# KNX-MultiExt.net
KiCad netlist of a schematic drawn in Altium Designer
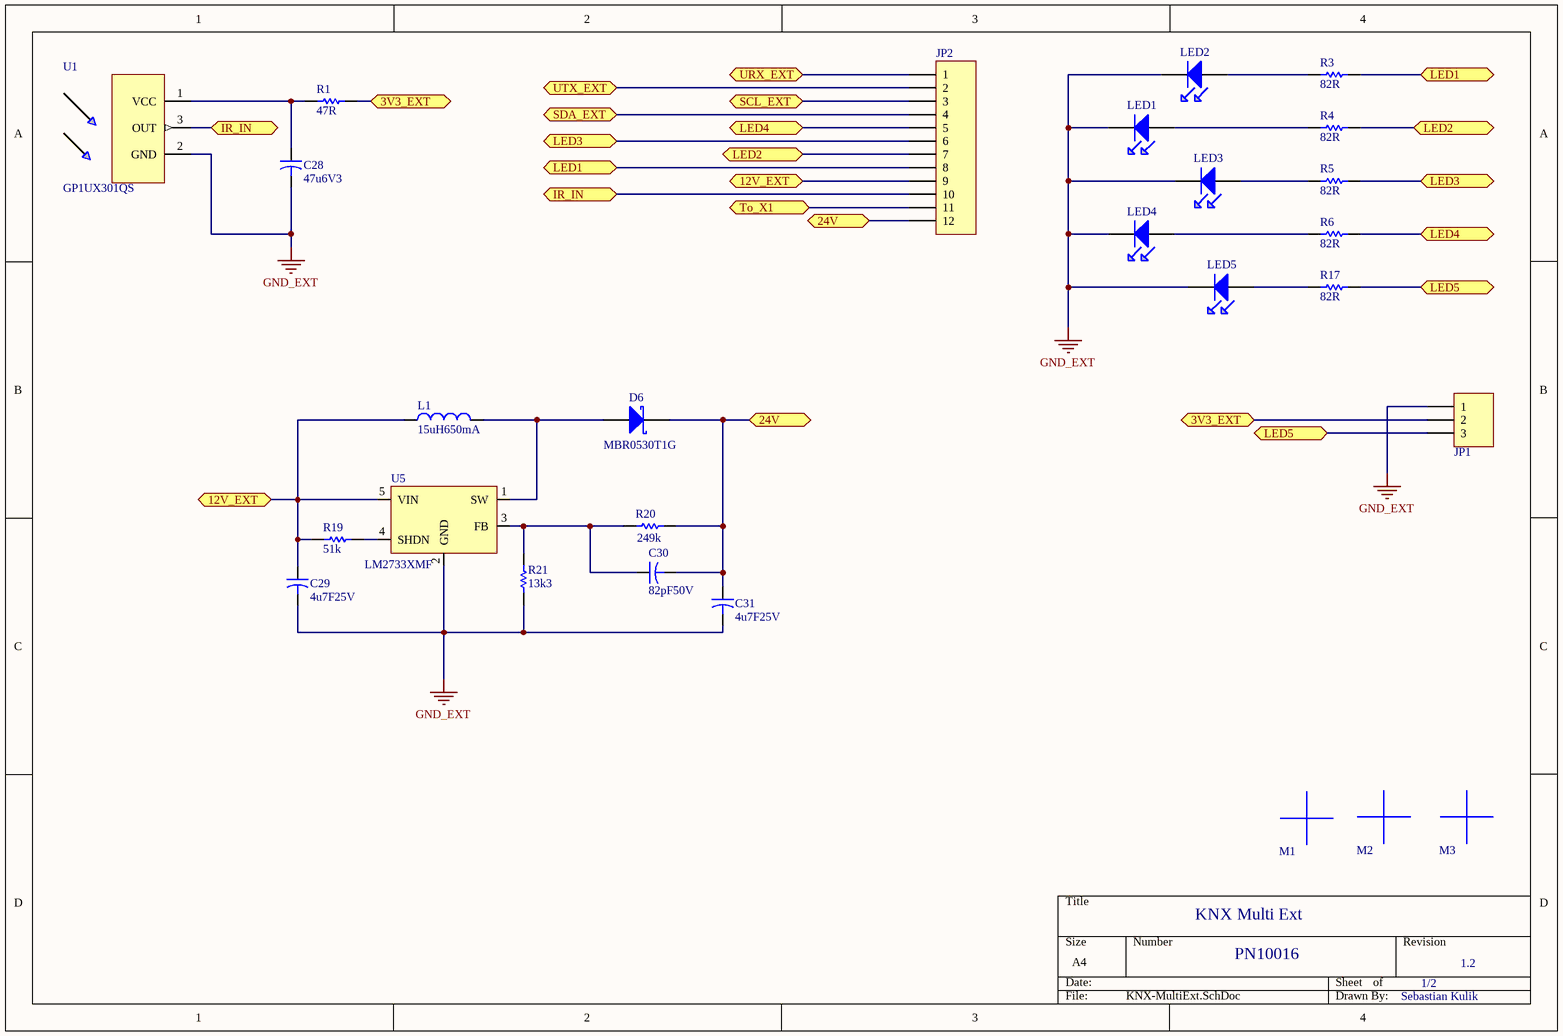
[diagram p0: KNX-MultiExt.SchDoc]

(export (version "E")
  (design (tool "Eeschema 10.0.6"))
  (components
    (comp (ref "C28")
      (value "47u6V3")
      (footprint "C0805")
      (description "Kemet  C series, X5R, 20%, 6.3V")
      (fields
        (field (name "MANUFACTURER") "Kemet")
        (field (name "Comment") "47u6V3_0805")
        (field (name "PUBLISHER") "Sebastian Kulik")
      )
      (libsource (lib "Capacitors") (part "47u6V3_0805"))
    )
    (comp (ref "C29")
      (value "4u7F25V")
      (footprint "C0805")
      (description "GRM series, X5R, 10%, 25V")
      (fields
        (field (name "MANUFACTURER") "Murata")
        (field (name "Comment") "4u7F25V_0805_Murata")
        (field (name "PUBLISHER") "Sebastian Kulik")
      )
      (libsource (lib "Capacitors") (part "4u7F25V_0805_Murata"))
    )
    (comp (ref "C30")
      (value "82pF50V")
      (footprint "C0805")
      (description "C0G series, 5%, 50V")
      (fields
        (field (name "MANUFACTURER") "AVX")
        (field (name "Comment") "82pF50V_0805")
        (field (name "PUBLISHER") "Sebastian Kulik")
      )
      (libsource (lib "Capacitors") (part "82pF50V_0805"))
    )
    (comp (ref "C31")
      (value "4u7F25V")
      (footprint "C0805")
      (description "GRM series, X7R, 10%, 50V")
      (fields
        (field (name "MANUFACTURER") "Murata")
        (field (name "Comment") "4u7F25V_0805_Murata_X7")
        (field (name "PUBLISHER") "Sebastian Kulik")
      )
      (libsource (lib "Capacitors") (part "4u7F25V_0805_Murata_X7"))
    )
    (comp (ref "D6")
      (value "MBR0530T1G")
      (footprint "SOD123")
      (description "Diode Schottky,2A,40V")
      (fields (field (name "MANUFACTURER") "Rohm") (field (name "PUBLISHER") "Sebastian Kulik"))
      (libsource (lib "Discrete") (part "MBR0530T1G"))
    )
    (comp (ref "JP1")
      (value "Plug_3_90_2.54")
      (footprint "HDR1X3-DOWN")
      (description "Plug,-3-Pin")
      (fields (field (name "MANUFACTURER") "WE") (field (name "PUBLISHER") "Sebastian Kulik"))
      (libsource (lib "Connectors") (part "Plug_3_90_2.54"))
    )
    (comp (ref "JP2")
      (value "Plug_12_90_2.54")
      (footprint "HDR1X12_2.54-Down")
      (description "Plug, 11-Pin")
      (fields (field (name "MANUFACTURER") "WE") (field (name "PUBLISHER") "Sebastian Kulik"))
      (libsource (lib "Connectors") (part "Plug_12_90_2.54"))
    )
    (comp (ref "L1")
      (value "15uH650mA")
      (footprint "WE-TPC-3816")
      (description "Coil, 15uH, 0.65A")
      (fields
        (field (name "MANUFACTURER") "WE")
        (field (name "Comment") "15uH-WE-TPC")
        (field (name "PUBLISHER") "Sebastian Kulik")
      )
      (libsource (lib "Passives") (part "15uH-WE-TPC"))
    )
    (comp (ref "LED1")
      (value "HSMG-120-Y")
      (footprint "HSMA-120-OR")
      (description "LED, 90°, yellow")
      (fields (field (name "MANUFACTURER") "Avago") (field (name "PUBLISHER") "Sebastian Kulik"))
      (libsource (lib "Discrete") (part "HSMG-120-Y"))
    )
    (comp (ref "LED2")
      (value "HSMG-120-GR")
      (footprint "HSMA-120-G")
      (description "LED, 90°, green")
      (fields (field (name "MANUFACTURER") "Avago") (field (name "PUBLISHER") "Sebastian Kulik"))
      (libsource (lib "Discrete") (part "HSMG-120-GR"))
    )
    (comp (ref "LED3")
      (value "HSMG-120-Y")
      (footprint "HSMA-120-OR")
      (description "LED, 90°, yellow")
      (fields (field (name "MANUFACTURER") "Avago") (field (name "PUBLISHER") "Sebastian Kulik"))
      (libsource (lib "Discrete") (part "HSMG-120-Y"))
    )
    (comp (ref "LED4")
      (value "HSMG-120-Y")
      (footprint "HSMA-120-OR")
      (description "LED, 90°, yellow")
      (fields (field (name "MANUFACTURER") "Avago") (field (name "PUBLISHER") "Sebastian Kulik"))
      (libsource (lib "Discrete") (part "HSMG-120-Y"))
    )
    (comp (ref "LED5")
      (value "HSMG-120-Y")
      (footprint "HSMA-120-OR")
      (description "LED, 90°, yellow")
      (fields (field (name "MANUFACTURER") "Avago") (field (name "PUBLISHER") "Sebastian Kulik"))
      (libsource (lib "Discrete") (part "HSMG-120-Y"))
    )
    (comp (ref "M1") (value "Mark") (footprint "Mark-3mm") (libsource (lib "Symbols") (part "Mark")))
    (comp (ref "M2") (value "Mark") (footprint "Mark-3mm") (libsource (lib "Symbols") (part "Mark")))
    (comp (ref "M3") (value "Mark") (footprint "Mark-3mm") (libsource (lib "Symbols") (part "Mark")))
    (comp (ref "R1")
      (value "47R")
      (footprint "R0603(1608)")
      (description "Vishay, CRCW series, 100mW, 1%")
      (fields
        (field (name "MANUFACTURER") "Vishay")
        (field (name "Comment") "47R_0603")
        (field (name "PUBLISHER") "Sebastian Kulik")
      )
      (libsource (lib "Resistors") (part "47R_0603"))
    )
    (comp (ref "R3")
      (value "82R")
      (footprint "R0603(1608)")
      (description "Vishay, CRCW series, 100mW, 1%")
      (fields
        (field (name "MANUFACTURER") "Vishay")
        (field (name "Comment") "82R_0603")
        (field (name "PUBLISHER") "Sebastian Kulik")
      )
      (libsource (lib "Resistors") (part "82R_0603"))
    )
    (comp (ref "R4")
      (value "82R")
      (footprint "R0603(1608)")
      (description "Vishay, CRCW series, 100mW, 1%")
      (fields
        (field (name "MANUFACTURER") "Vishay")
        (field (name "Comment") "82R_0603")
        (field (name "PUBLISHER") "Sebastian Kulik")
      )
      (libsource (lib "Resistors") (part "82R_0603"))
    )
    (comp (ref "R5")
      (value "82R")
      (footprint "R0603(1608)")
      (description "Vishay, CRCW series, 100mW, 1%")
      (fields
        (field (name "MANUFACTURER") "Vishay")
        (field (name "Comment") "82R_0603")
        (field (name "PUBLISHER") "Sebastian Kulik")
      )
      (libsource (lib "Resistors") (part "82R_0603"))
    )
    (comp (ref "R6")
      (value "82R")
      (footprint "R0603(1608)")
      (description "Vishay, CRCW series, 100mW, 1%")
      (fields
        (field (name "MANUFACTURER") "Vishay")
        (field (name "Comment") "82R_0603")
        (field (name "PUBLISHER") "Sebastian Kulik")
      )
      (libsource (lib "Resistors") (part "82R_0603"))
    )
    (comp (ref "R17")
      (value "82R")
      (footprint "R0603(1608)")
      (description "Vishay, CRCW series, 100mW, 1%")
      (fields
        (field (name "MANUFACTURER") "Vishay")
        (field (name "Comment") "82R_0603")
        (field (name "PUBLISHER") "Sebastian Kulik")
      )
      (libsource (lib "Resistors") (part "82R_0603"))
    )
    (comp (ref "R19")
      (value "51k")
      (footprint "R0402")
      (description "Vishay CRCW series, 63mW, 1%")
      (fields
        (field (name "MANUFACTURER") "Vishay")
        (field (name "Comment") "51k_0402")
        (field (name "PUBLISHER") "Sebastian Kulik")
      )
      (libsource (lib "Resistors") (part "51k_0402"))
    )
    (comp (ref "R20")
      (value "249k")
      (footprint "R0402")
      (description "Vishay CRCW series, 63mW, 1%")
      (fields
        (field (name "MANUFACTURER") "Vishay")
        (field (name "Comment") "249k_0402")
        (field (name "PUBLISHER") "Sebastian Kulik")
      )
      (libsource (lib "Resistors") (part "249k_0402"))
    )
    (comp (ref "R21")
      (value "13k3")
      (footprint "R0402")
      (description "Vishay CRCW series, 63mW, 1%")
      (fields
        (field (name "MANUFACTURER") "Vishay")
        (field (name "Comment") "13k3_0402")
        (field (name "PUBLISHER") "Sebastian Kulik")
      )
      (libsource (lib "Resistors") (part "13k3_0402"))
    )
    (comp (ref "U1")
      (value "GP1UX301QS")
      (footprint "IR-GP")
      (description "IR reseiver")
      (fields (field (name "MANUFACTURER") "Sharp") (field (name "PUBLISHER") "Sebastian Kulik"))
      (libsource (lib "ICs") (part "GP1UX301QS"))
    )
    (comp (ref "U5")
      (value "LM2733XMF")
      (footprint "PDSO-G5")
      (description "TI, buck boost converter, 1A max")
      (fields (field (name "MANUFACTURER") "TI") (field (name "PUBLISHER") "Sebastian Kulik"))
      (libsource (lib "ICs") (part "LM2733XMF"))
    )
  )
  (nets
    (net (code "1") (name "/3V3_EXT") (class "Default")
      (node (ref "JP1") (pin "2") (pinfunction "2_2") (pintype "passive"))
      (node (ref "R1") (pin "2") (pinfunction "2_2") (pintype "passive"))
    )
    (net (code "2") (name "/12V_EXT") (class "Default")
      (node (ref "C29") (pin "1") (pinfunction "1_1") (pintype "passive"))
      (node (ref "JP2") (pin "9") (pinfunction "9_9") (pintype "passive"))
      (node (ref "L1") (pin "1") (pinfunction "1_1") (pintype "passive"))
      (node (ref "R19") (pin "1") (pinfunction "1_1") (pintype "passive"))
      (node (ref "U5") (pin "5") (pinfunction "VIN_5") (pintype "passive"))
    )
    (net (code "3") (name "/24V") (class "Default")
      (node (ref "C30") (pin "2") (pinfunction "2_2") (pintype "passive"))
      (node (ref "C31") (pin "1") (pinfunction "1_1") (pintype "passive"))
      (node (ref "D6") (pin "1") (pinfunction "K_1") (pintype "passive"))
      (node (ref "JP2") (pin "12") (pinfunction "12_12") (pintype "passive"))
      (node (ref "R20") (pin "2") (pinfunction "2_2") (pintype "passive"))
    )
    (net (code "4") (name "/IR_IN") (class "Default")
      (node (ref "JP2") (pin "10") (pinfunction "10_10") (pintype "passive"))
      (node (ref "U1") (pin "3") (pinfunction "OUT_3") (pintype "output"))
    )
    (net (code "5") (name "/LED1") (class "Default")
      (node (ref "JP2") (pin "8") (pinfunction "8_8") (pintype "passive"))
      (node (ref "R3") (pin "2") (pinfunction "2_2") (pintype "passive"))
    )
    (net (code "6") (name "/LED2") (class "Default")
      (node (ref "JP2") (pin "7") (pinfunction "7_7") (pintype "passive"))
      (node (ref "R4") (pin "2") (pinfunction "2_2") (pintype "passive"))
    )
    (net (code "7") (name "/LED3") (class "Default")
      (node (ref "JP2") (pin "6") (pinfunction "6_6") (pintype "passive"))
      (node (ref "R5") (pin "2") (pinfunction "2_2") (pintype "passive"))
    )
    (net (code "8") (name "/LED4") (class "Default")
      (node (ref "JP2") (pin "5") (pinfunction "5_5") (pintype "passive"))
      (node (ref "R6") (pin "2") (pinfunction "2_2") (pintype "passive"))
    )
    (net (code "9") (name "/LED5") (class "Default")
      (node (ref "JP1") (pin "3") (pinfunction "3_3") (pintype "passive"))
      (node (ref "R17") (pin "2") (pinfunction "2_2") (pintype "passive"))
    )
    (net (code "10") (name "/SCL_EXT") (class "Default")
      (node (ref "JP2") (pin "3") (pinfunction "3_3") (pintype "passive"))
    )
    (net (code "11") (name "/SDA_EXT") (class "Default")
      (node (ref "JP2") (pin "4") (pinfunction "4_4") (pintype "passive"))
    )
    (net (code "12") (name "/To_X1") (class "Default")
      (node (ref "JP2") (pin "11") (pinfunction "11_11") (pintype "passive"))
    )
    (net (code "13") (name "/URX_EXT") (class "Default")
      (node (ref "JP2") (pin "1") (pinfunction "1_1") (pintype "passive"))
    )
    (net (code "14") (name "/UTX_EXT") (class "Default")
      (node (ref "JP2") (pin "2") (pinfunction "2_2") (pintype "passive"))
    )
    (net (code "15") (name "GND_EXT") (class "Default")
      (node (ref "C28") (pin "2") (pinfunction "2_2") (pintype "passive"))
      (node (ref "C29") (pin "2") (pinfunction "2_2") (pintype "passive"))
      (node (ref "C31") (pin "2") (pinfunction "2_2") (pintype "passive"))
      (node (ref "JP1") (pin "1") (pinfunction "1_1") (pintype "passive"))
      (node (ref "LED1") (pin "1") (pinfunction "K_1") (pintype "passive"))
      (node (ref "LED2") (pin "1") (pinfunction "K_1") (pintype "passive"))
      (node (ref "LED3") (pin "1") (pinfunction "K_1") (pintype "passive"))
      (node (ref "LED4") (pin "1") (pinfunction "K_1") (pintype "passive"))
      (node (ref "LED5") (pin "1") (pinfunction "K_1") (pintype "passive"))
      (node (ref "R21") (pin "1") (pinfunction "1_1") (pintype "passive"))
      (node (ref "U1") (pin "2") (pinfunction "GND_2") (pintype "power_in"))
      (node (ref "U5") (pin "2") (pinfunction "GND_2") (pintype "passive"))
    )
    (net (code "16") (name "Net-(D6-A)") (class "Default")
      (node (ref "D6") (pin "2") (pinfunction "A_2") (pintype "passive"))
      (node (ref "L1") (pin "2") (pinfunction "2_2") (pintype "passive"))
      (node (ref "U5") (pin "1") (pinfunction "SW_1") (pintype "power_in"))
    )
    (net (code "17") (name "Net-(LED1-A)") (class "Default")
      (node (ref "LED1") (pin "2") (pinfunction "A_2") (pintype "passive"))
      (node (ref "R4") (pin "1") (pinfunction "1_1") (pintype "passive"))
    )
    (net (code "18") (name "Net-(LED2-A)") (class "Default")
      (node (ref "LED2") (pin "2") (pinfunction "A_2") (pintype "passive"))
      (node (ref "R3") (pin "1") (pinfunction "1_1") (pintype "passive"))
    )
    (net (code "19") (name "Net-(LED3-A)") (class "Default")
      (node (ref "LED3") (pin "2") (pinfunction "A_2") (pintype "passive"))
      (node (ref "R5") (pin "1") (pinfunction "1_1") (pintype "passive"))
    )
    (net (code "20") (name "Net-(LED4-A)") (class "Default")
      (node (ref "LED4") (pin "2") (pinfunction "A_2") (pintype "passive"))
      (node (ref "R6") (pin "1") (pinfunction "1_1") (pintype "passive"))
    )
    (net (code "21") (name "Net-(LED5-A)") (class "Default")
      (node (ref "LED5") (pin "2") (pinfunction "A_2") (pintype "passive"))
      (node (ref "R17") (pin "1") (pinfunction "1_1") (pintype "passive"))
    )
    (net (code "22") (name "Net-(U1-VCC)") (class "Default")
      (node (ref "C28") (pin "1") (pinfunction "1_1") (pintype "passive"))
      (node (ref "R1") (pin "1") (pinfunction "1_1") (pintype "passive"))
      (node (ref "U1") (pin "1") (pinfunction "VCC_1") (pintype "power_in"))
    )
    (net (code "23") (name "Net-(U5-FB)") (class "Default")
      (node (ref "C30") (pin "1") (pinfunction "1_1") (pintype "passive"))
      (node (ref "R20") (pin "1") (pinfunction "1_1") (pintype "passive"))
      (node (ref "R21") (pin "2") (pinfunction "2_2") (pintype "passive"))
      (node (ref "U5") (pin "3") (pinfunction "FB_3") (pintype "passive"))
    )
    (net (code "24") (name "Net-(U5-SHDN)") (class "Default")
      (node (ref "R19") (pin "2") (pinfunction "2_2") (pintype "passive"))
      (node (ref "U5") (pin "4") (pinfunction "SHDN_4") (pintype "passive"))
    )
  )
)
